# IN_OUT.net
KiCad netlist of a schematic drawn in EasyEDA
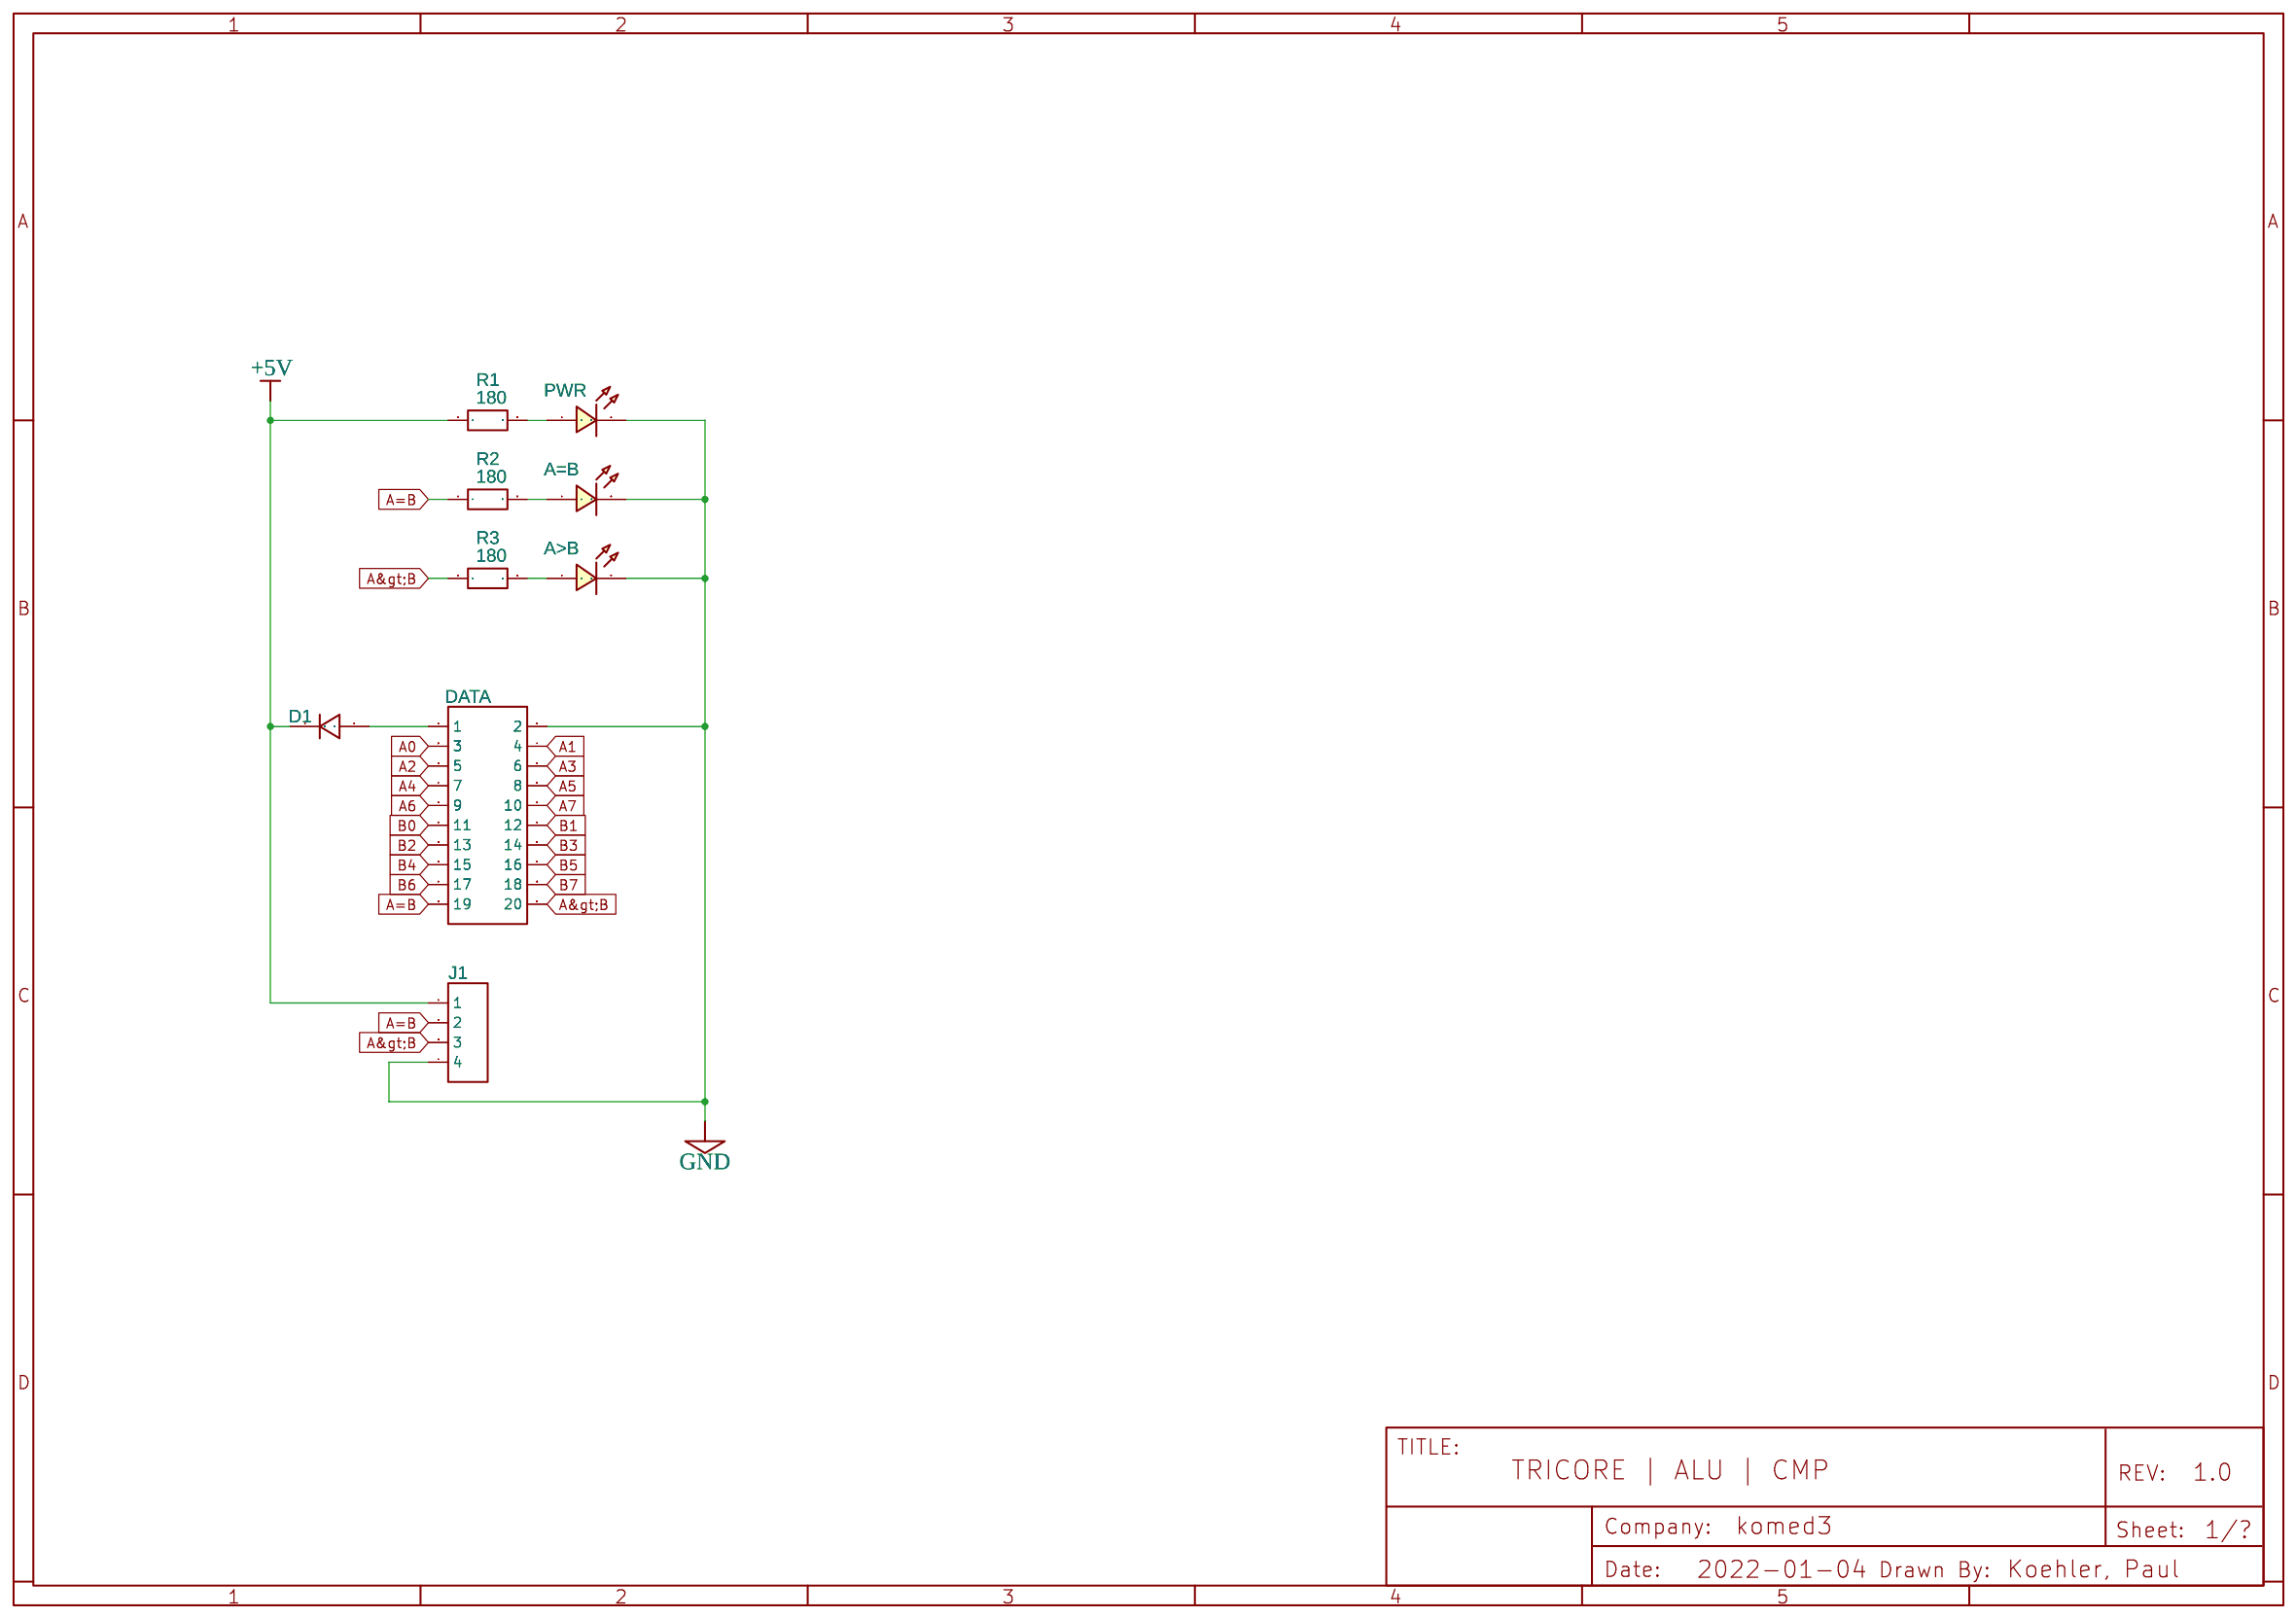
[diagram p0: schematic sheet]

(export (version "E")
  (design (tool "Eeschema 10.0.6"))
  (components
    (comp (ref "A=B")
      (value "LED-TH-5mm_R")
      (fields
        (field (name "BOM_Manufacturer Part") "333-2SURD/S530-A3")
        (field (name "BOM_Supplier Part") "C87271")
      )
      (libsource (lib "") (part "LED-TH-5mm_R_2"))
    )
    (comp (ref "A>B")
      (value "LED-TH-5mm_R")
      (fields
        (field (name "BOM_Manufacturer Part") "333-2SURD/S530-A3")
        (field (name "BOM_Supplier Part") "C87271")
      )
      (libsource (lib "") (part "LED-TH-5mm_R_1"))
    )
    (comp (ref "D1")
      (value "1N4007")
      (fields (field (name "BOM_Supplier Part") "C106903"))
      (libsource (lib "") (part "1N4007"))
    )
    (comp (ref "DATA")
      (value "HDR-IDC-2.54-2X10P")
      (fields
        (field (name "BOM_Manufacturer Part") "IDC Box 2.54mm 2X10P　Straight")
        (field (name "BOM_Supplier Part") "C3405")
      )
      (libsource (lib "") (part "HDR-IDC-2.54-2X10P"))
    )
    (comp (ref "J1")
      (value "HDR-M-2.54_1x4")
      (fields (field (name "BOM_Supplier Part") "C124378"))
      (libsource (lib "") (part "HDR-M-2.54_1x4"))
    )
    (comp (ref "PWR")
      (value "LED-TH-5mm_R")
      (fields
        (field (name "BOM_Manufacturer Part") "333-2SURD/S530-A3")
        (field (name "BOM_Supplier Part") "C87271")
      )
      (libsource (lib "") (part "LED-TH-5mm_R"))
    )
    (comp (ref "R1") (value "180") (libsource (lib "") (part "R_AXIAL-0.3_EU")))
    (comp (ref "R2") (value "180") (libsource (lib "") (part "R_AXIAL-0.3_EU")))
    (comp (ref "R3") (value "180") (libsource (lib "") (part "R_AXIAL-0.3_EU")))
  )
  (nets
    (net (code "1") (name "+5V") (class "Default")
      (node (ref "D1") (pin "1") (pinfunction "1_1") (pintype "unspecified"))
      (node (ref "J1") (pin "1") (pinfunction "1_1") (pintype "unspecified"))
      (node (ref "R1") (pin "1") (pinfunction "1_1") (pintype "unspecified"))
    )
    (net (code "2") (name "A&gt;B") (class "Default")
      (node (ref "DATA") (pin "20") (pinfunction "20_20") (pintype "unspecified"))
      (node (ref "J1") (pin "3") (pinfunction "3_3") (pintype "unspecified"))
      (node (ref "R3") (pin "1") (pinfunction "1_1") (pintype "unspecified"))
    )
    (net (code "3") (name "A0") (class "Default")
      (node (ref "DATA") (pin "3") (pinfunction "3_3") (pintype "unspecified"))
    )
    (net (code "4") (name "A1") (class "Default")
      (node (ref "DATA") (pin "4") (pinfunction "4_4") (pintype "unspecified"))
    )
    (net (code "5") (name "A2") (class "Default")
      (node (ref "DATA") (pin "5") (pinfunction "5_5") (pintype "unspecified"))
    )
    (net (code "6") (name "A3") (class "Default")
      (node (ref "DATA") (pin "6") (pinfunction "6_6") (pintype "unspecified"))
    )
    (net (code "7") (name "A4") (class "Default")
      (node (ref "DATA") (pin "7") (pinfunction "7_7") (pintype "unspecified"))
    )
    (net (code "8") (name "A5") (class "Default")
      (node (ref "DATA") (pin "8") (pinfunction "8_8") (pintype "unspecified"))
    )
    (net (code "9") (name "A6") (class "Default")
      (node (ref "DATA") (pin "9") (pinfunction "9_9") (pintype "unspecified"))
    )
    (net (code "10") (name "A7") (class "Default")
      (node (ref "DATA") (pin "10") (pinfunction "10_10") (pintype "unspecified"))
    )
    (net (code "11") (name "A=B") (class "Default")
      (node (ref "DATA") (pin "19") (pinfunction "19_19") (pintype "unspecified"))
      (node (ref "J1") (pin "2") (pinfunction "2_2") (pintype "unspecified"))
      (node (ref "R2") (pin "1") (pinfunction "1_1") (pintype "unspecified"))
    )
    (net (code "12") (name "B0") (class "Default")
      (node (ref "DATA") (pin "11") (pinfunction "11_11") (pintype "unspecified"))
    )
    (net (code "13") (name "B1") (class "Default")
      (node (ref "DATA") (pin "12") (pinfunction "12_12") (pintype "unspecified"))
    )
    (net (code "14") (name "B2") (class "Default")
      (node (ref "DATA") (pin "13") (pinfunction "13_13") (pintype "unspecified"))
    )
    (net (code "15") (name "B3") (class "Default")
      (node (ref "DATA") (pin "14") (pinfunction "14_14") (pintype "unspecified"))
    )
    (net (code "16") (name "B4") (class "Default")
      (node (ref "DATA") (pin "15") (pinfunction "15_15") (pintype "unspecified"))
    )
    (net (code "17") (name "B5") (class "Default")
      (node (ref "DATA") (pin "16") (pinfunction "16_16") (pintype "unspecified"))
    )
    (net (code "18") (name "B6") (class "Default")
      (node (ref "DATA") (pin "17") (pinfunction "17_17") (pintype "unspecified"))
    )
    (net (code "19") (name "B7") (class "Default")
      (node (ref "DATA") (pin "18") (pinfunction "18_18") (pintype "unspecified"))
    )
    (net (code "20") (name "GND") (class "Default")
      (node (ref "A=B") (pin "2") (pinfunction "2_2") (pintype "unspecified"))
      (node (ref "A>B") (pin "2") (pinfunction "2_2") (pintype "unspecified"))
      (node (ref "DATA") (pin "2") (pinfunction "2_2") (pintype "unspecified"))
      (node (ref "J1") (pin "4") (pinfunction "4_4") (pintype "unspecified"))
      (node (ref "PWR") (pin "2") (pinfunction "2_2") (pintype "unspecified"))
    )
    (net (code "21") (name "Net-(A=B-Pad1)") (class "Default")
      (node (ref "A=B") (pin "1") (pinfunction "1_1") (pintype "unspecified"))
      (node (ref "R2") (pin "2") (pinfunction "2_2") (pintype "unspecified"))
    )
    (net (code "22") (name "Net-(A>B-Pad1)") (class "Default")
      (node (ref "A>B") (pin "1") (pinfunction "1_1") (pintype "unspecified"))
      (node (ref "R3") (pin "2") (pinfunction "2_2") (pintype "unspecified"))
    )
    (net (code "23") (name "Net-(D1-Pad2)") (class "Default")
      (node (ref "D1") (pin "2") (pinfunction "2_2") (pintype "unspecified"))
      (node (ref "DATA") (pin "1") (pinfunction "1_1") (pintype "unspecified"))
    )
    (net (code "24") (name "Net-(PWR-Pad1)") (class "Default")
      (node (ref "PWR") (pin "1") (pinfunction "1_1") (pintype "unspecified"))
      (node (ref "R1") (pin "2") (pinfunction "2_2") (pintype "unspecified"))
    )
  )
)
